# Schematic.net
KiCad netlist of a schematic drawn in Altium Designer
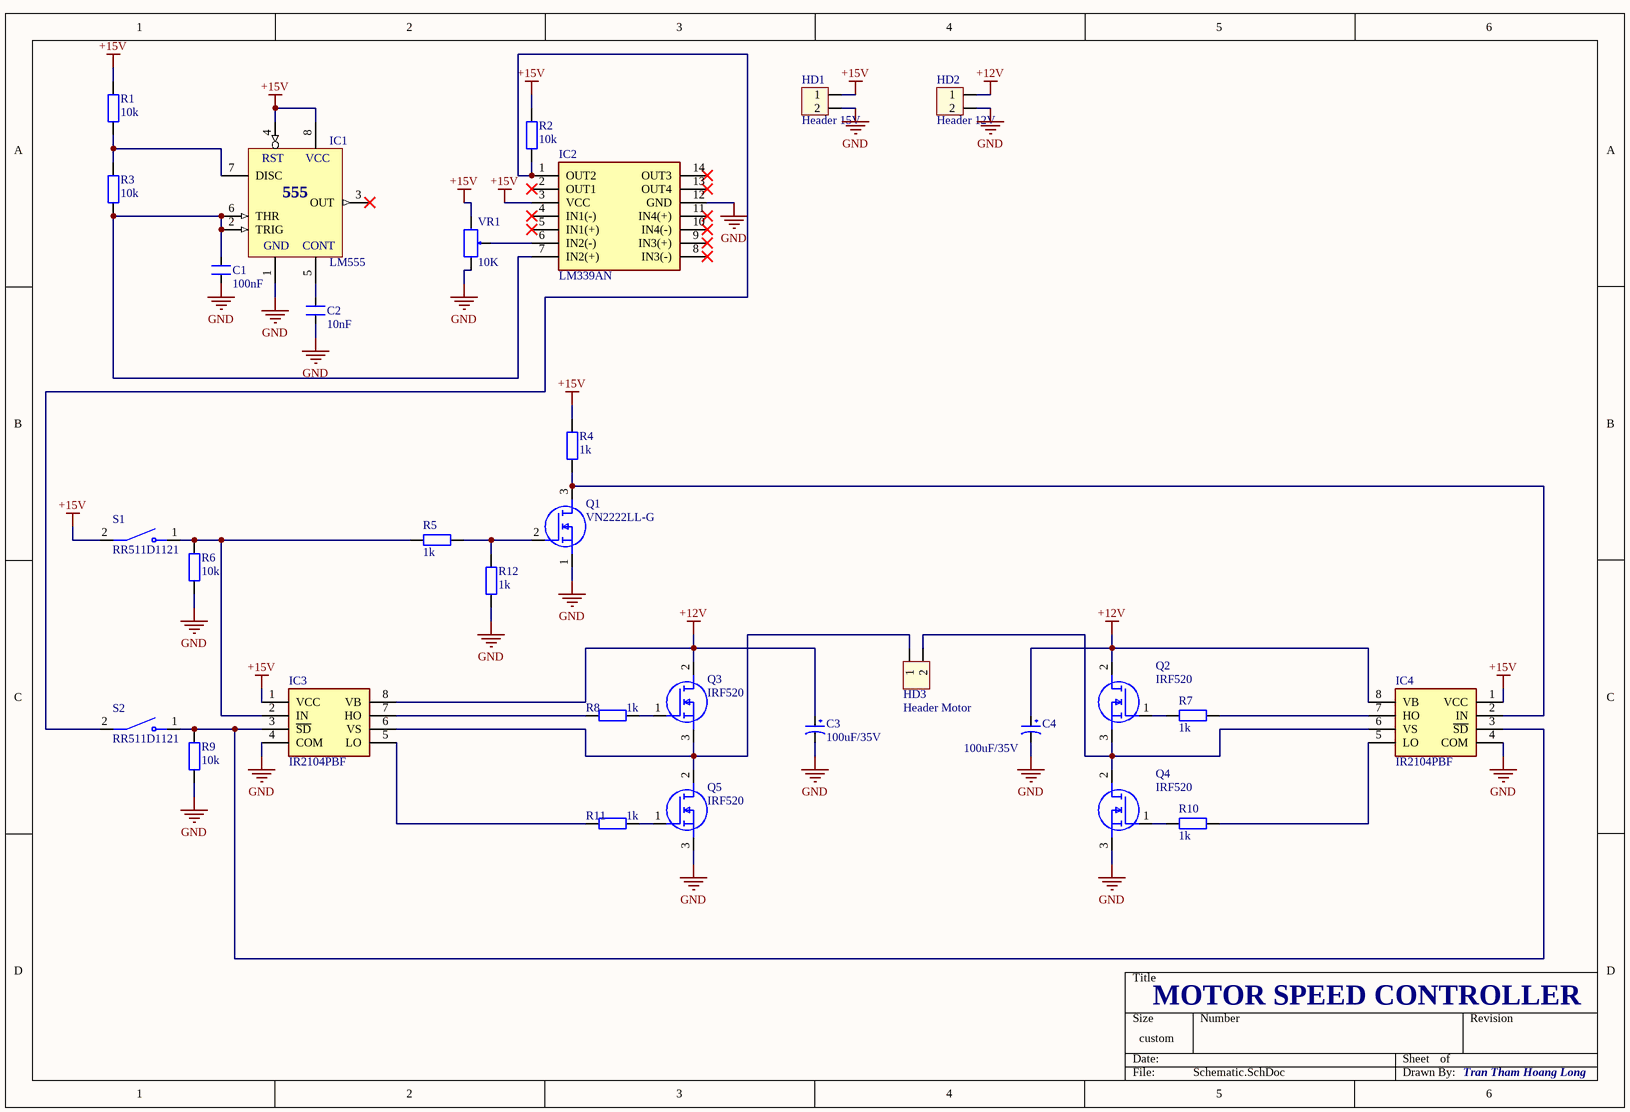
[diagram p0: Schematic.SchDoc]

(export (version "E")
  (design (tool "Eeschema 10.0.6"))
  (components
    (comp (ref "C1")
      (value "100nF")
      (footprint "CN1")
      (description "Cap np  1pF - 472pF")
      (libsource (lib "syhaunguyen") (part "CN1"))
    )
    (comp (ref "C2")
      (value "10nF")
      (footprint "CN1")
      (description "Cap np  1pF - 472pF")
      (libsource (lib "syhaunguyen") (part "CN1"))
    )
    (comp (ref "C3")
      (value "100uF/35V")
      (footprint "CP1.5/3.4")
      (description "Cap 100uF/35V - 470uF/16V")
      (libsource (lib "syhaunguyen") (part "CP3"))
    )
    (comp (ref "C4")
      (value "100uF/35V")
      (footprint "CP1.5/3.4")
      (description "Cap 100uF/35V - 470uF/16V")
      (libsource (lib "syhaunguyen") (part "CP3"))
    )
    (comp (ref "HD1")
      (value "Header 15V")
      (footprint "HED2")
      (description "Header 2 (Green)")
      (libsource (lib "syhaunguyen") (part "Hed2"))
    )
    (comp (ref "HD2")
      (value "Header 12V")
      (footprint "HED2")
      (description "Header 2 (Green)")
      (libsource (lib "syhaunguyen") (part "Hed2"))
    )
    (comp (ref "HD3")
      (value "Header Motor")
      (footprint "HED2")
      (description "Header 2 (Green)")
      (libsource (lib "") (part "Hed2_1"))
    )
    (comp (ref "IC1")
      (value "LM555")
      (footprint "DIP8/W0.3")
      (description "Timer")
      (libsource (lib "syhaunguyen") (part "LM555"))
    )
    (comp (ref "IC2")
      (value "LM339AN")
      (footprint "SamacSys:DIP794W56P254L1918H533Q14N")
      (description "Integrated Circuit")
      (fields (field (name "MOUSER PART NUMBER") "512-LM339AN"))
      (libsource (lib "*") (part "LM339AN"))
    )
    (comp (ref "IC3")
      (value "IR2104PBF")
      (footprint "SamacSys:DIP762W56P254L988H533Q8N")
      (description "Integrated Circuit")
      (fields (field (name "MOUSER PART NUMBER") "942-IR2104PBF"))
      (libsource (lib "") (part "IR2104PBF_1"))
    )
    (comp (ref "IC4")
      (value "IR2104PBF")
      (footprint "SamacSys:DIP762W56P254L988H533Q8N")
      (description "Integrated Circuit")
      (fields (field (name "MOUSER PART NUMBER") "942-IR2104PBF"))
      (libsource (lib "*") (part "IR2104PBF"))
    )
    (comp (ref "Q1")
      (value "VN2222LL-G")
      (footprint "QTO-92A")
      (description "MOSFET (N-Channel)")
      (fields (field (name "MOUSER PART NUMBER") "689-VN2222LL-G"))
      (libsource (lib "*") (part "VN2222LL-G"))
    )
    (comp (ref "Q2")
      (value "IRF520")
      (footprint "QTO-220H3")
      (description "MOSFET (N-Channel)")
      (fields (field (name "MOUSER PART NUMBER") "511-IRF520"))
      (libsource (lib "SamacSys") (part "IRF520"))
    )
    (comp (ref "Q3")
      (value "IRF520")
      (footprint "QTO-220H3")
      (description "MOSFET (N-Channel)")
      (fields (field (name "MOUSER PART NUMBER") "511-IRF520"))
      (libsource (lib "SamacSys") (part "IRF520"))
    )
    (comp (ref "Q4")
      (value "IRF520")
      (footprint "QTO-220H3")
      (description "MOSFET (N-Channel)")
      (fields (field (name "MOUSER PART NUMBER") "511-IRF520"))
      (libsource (lib "SamacSys") (part "IRF520"))
    )
    (comp (ref "Q5")
      (value "IRF520")
      (footprint "QTO-220H3")
      (description "MOSFET (N-Channel)")
      (fields (field (name "MOUSER PART NUMBER") "511-IRF520"))
      (libsource (lib "SamacSys") (part "IRF520"))
    )
    (comp (ref "R1")
      (value "10k")
      (footprint "R1/4W")
      (description "Resistor 1/4W")
      (libsource (lib "syhaunguyen") (part "R1/4W"))
    )
    (comp (ref "R2")
      (value "10k")
      (footprint "R1/4W")
      (description "Resistor 1/4W")
      (libsource (lib "syhaunguyen") (part "R1/4W"))
    )
    (comp (ref "R3")
      (value "10k")
      (footprint "R1/4W")
      (description "Resistor 1/4W")
      (libsource (lib "syhaunguyen") (part "R1/4W"))
    )
    (comp (ref "R4")
      (value "1k")
      (footprint "R1/4W")
      (description "Resistor 1/4W")
      (libsource (lib "syhaunguyen") (part "R1/4W"))
    )
    (comp (ref "R5")
      (value "1k")
      (footprint "R1/4W")
      (description "Resistor 1/4W")
      (libsource (lib "syhaunguyen") (part "R1/4W"))
    )
    (comp (ref "R6")
      (value "10k")
      (footprint "R1/4W")
      (description "Resistor 1/4W")
      (libsource (lib "syhaunguyen") (part "R1/4W"))
    )
    (comp (ref "R7")
      (value "1k")
      (footprint "R1/4W")
      (description "Resistor 1/4W")
      (libsource (lib "syhaunguyen") (part "R1/4W"))
    )
    (comp (ref "R8")
      (value "1k")
      (footprint "R1/4W")
      (description "Resistor 1/4W")
      (libsource (lib "syhaunguyen") (part "R1/4W"))
    )
    (comp (ref "R9")
      (value "10k")
      (footprint "R1/4W")
      (description "Resistor 1/4W")
      (libsource (lib "syhaunguyen") (part "R1/4W"))
    )
    (comp (ref "R10")
      (value "1k")
      (footprint "R1/4W")
      (description "Resistor 1/4W")
      (libsource (lib "syhaunguyen") (part "R1/4W"))
    )
    (comp (ref "R11")
      (value "1k")
      (footprint "R1/4W")
      (description "Resistor 1/4W")
      (libsource (lib "syhaunguyen") (part "R1/4W"))
    )
    (comp (ref "R12")
      (value "1k")
      (footprint "R1/4W")
      (description "Resistor 1/4W")
      (libsource (lib "syhaunguyen") (part "R1/4W"))
    )
    (comp (ref "S1")
      (value "RR511D1121")
      (footprint "E-SWITCH_RR511D1121")
      (description "Rocker Switch, RR5 Series, SPST,OFF-ON,Blk Rocker,I/O Legend, 20A, 125VAC, QC")
      (fields (field (name "MF") "E-Switch"))
      (libsource (lib "RR511D1121") (part "RR511D1121"))
    )
    (comp (ref "S2")
      (value "RR511D1121")
      (footprint "E-SWITCH_RR511D1121")
      (description "Rocker Switch, RR5 Series, SPST,OFF-ON,Blk Rocker,I/O Legend, 20A, 125VAC, QC")
      (fields (field (name "MF") "E-Switch"))
      (libsource (lib "RR511D1121") (part "RR511D1121"))
    )
    (comp (ref "VR1")
      (value "10K")
      (footprint "VOL_1")
      (description "Var Resistor")
      (libsource (lib "Cty1") (part "Var Resitor"))
    )
  )
  (nets
    (net (code "1") (name "+12V") (class "Default")
      (node (ref "C3") (pin "1") (pinfunction "1_1") (pintype "passive"))
      (node (ref "C4") (pin "1") (pinfunction "1_1") (pintype "passive"))
      (node (ref "HD2") (pin "1") (pinfunction "1_1") (pintype "passive"))
      (node (ref "IC3") (pin "8") (pinfunction "VB_8") (pintype "passive"))
      (node (ref "IC4") (pin "8") (pinfunction "VB_8") (pintype "passive"))
      (node (ref "Q2") (pin "2") (pinfunction "D_2") (pintype "passive"))
      (node (ref "Q3") (pin "2") (pinfunction "D_2") (pintype "passive"))
    )
    (net (code "2") (name "+15V") (class "Default")
      (node (ref "HD1") (pin "1") (pinfunction "1_1") (pintype "passive"))
      (node (ref "IC1") (pin "4") (pinfunction "RST_4") (pintype "input"))
      (node (ref "IC1") (pin "8") (pinfunction "VCC_8") (pintype "power_in"))
      (node (ref "IC2") (pin "3") (pinfunction "VCC_3") (pintype "passive"))
      (node (ref "IC3") (pin "1") (pinfunction "VCC_1") (pintype "passive"))
      (node (ref "IC4") (pin "1") (pinfunction "VCC_1") (pintype "passive"))
      (node (ref "R1") (pin "2") (pinfunction "2_2") (pintype "passive"))
      (node (ref "R2") (pin "2") (pinfunction "2_2") (pintype "passive"))
      (node (ref "R4") (pin "1") (pinfunction "1_1") (pintype "passive"))
      (node (ref "S1") (pin "2") (pinfunction "COM_2") (pintype "passive"))
      (node (ref "VR1") (pin "1") (pinfunction "1_1") (pintype "passive"))
    )
    (net (code "3") (name "GND") (class "Default")
      (node (ref "C1") (pin "1") (pinfunction "1_1") (pintype "passive"))
      (node (ref "C2") (pin "1") (pinfunction "1_1") (pintype "passive"))
      (node (ref "C3") (pin "2") (pinfunction "2_2") (pintype "passive"))
      (node (ref "C4") (pin "2") (pinfunction "2_2") (pintype "passive"))
      (node (ref "HD1") (pin "2") (pinfunction "2_2") (pintype "passive"))
      (node (ref "HD2") (pin "2") (pinfunction "2_2") (pintype "passive"))
      (node (ref "IC1") (pin "1") (pinfunction "GND_1") (pintype "power_in"))
      (node (ref "IC2") (pin "12") (pinfunction "GND_12") (pintype "passive"))
      (node (ref "IC3") (pin "4") (pinfunction "COM_4") (pintype "passive"))
      (node (ref "IC4") (pin "4") (pinfunction "COM_4") (pintype "passive"))
      (node (ref "Q1") (pin "1") (pinfunction "S_1") (pintype "passive"))
      (node (ref "Q4") (pin "3") (pinfunction "S_3") (pintype "passive"))
      (node (ref "Q5") (pin "3") (pinfunction "S_3") (pintype "passive"))
      (node (ref "R12") (pin "2") (pinfunction "2_2") (pintype "passive"))
      (node (ref "R6") (pin "1") (pinfunction "1_1") (pintype "passive"))
      (node (ref "R9") (pin "1") (pinfunction "1_1") (pintype "passive"))
      (node (ref "VR1") (pin "3") (pinfunction "3_3") (pintype "passive"))
    )
    (net (code "4") (name "Net-(IC1-CONT)") (class "Default")
      (node (ref "C2") (pin "2") (pinfunction "2_2") (pintype "passive"))
      (node (ref "IC1") (pin "5") (pinfunction "CONT_5") (pintype "passive"))
    )
    (net (code "5") (name "Net-(IC1-DISC)") (class "Default")
      (node (ref "IC1") (pin "7") (pinfunction "DISC_7") (pintype "open_collector"))
      (node (ref "R1") (pin "1") (pinfunction "1_1") (pintype "passive"))
      (node (ref "R3") (pin "2") (pinfunction "2_2") (pintype "passive"))
    )
    (net (code "6") (name "Net-(IC1-THR)") (class "Default")
      (node (ref "C1") (pin "2") (pinfunction "2_2") (pintype "passive"))
      (node (ref "IC1") (pin "2") (pinfunction "TRIG_2") (pintype "input"))
      (node (ref "IC1") (pin "6") (pinfunction "THR_6") (pintype "input"))
      (node (ref "IC2") (pin "7") (pinfunction "IN2(+)_7") (pintype "passive"))
      (node (ref "R3") (pin "1") (pinfunction "1_1") (pintype "passive"))
    )
    (net (code "7") (name "Net-(IC2-IN2(-))") (class "Default")
      (node (ref "IC2") (pin "6") (pinfunction "IN2(-)_6") (pintype "passive"))
      (node (ref "VR1") (pin "2") (pinfunction "2_2") (pintype "passive"))
    )
    (net (code "8") (name "Net-(IC2-OUT2)") (class "Default")
      (node (ref "IC2") (pin "1") (pinfunction "OUT2_1") (pintype "passive"))
      (node (ref "R2") (pin "1") (pinfunction "1_1") (pintype "passive"))
      (node (ref "S2") (pin "2") (pinfunction "COM_2") (pintype "passive"))
    )
    (net (code "9") (name "Net-(IC3-HO)") (class "Default")
      (node (ref "IC3") (pin "7") (pinfunction "HO_7") (pintype "passive"))
      (node (ref "R8") (pin "2") (pinfunction "2_2") (pintype "passive"))
    )
    (net (code "10") (name "Net-(IC3-IN)") (class "Default")
      (node (ref "IC3") (pin "2") (pinfunction "IN_2") (pintype "passive"))
      (node (ref "R5") (pin "2") (pinfunction "2_2") (pintype "passive"))
      (node (ref "R6") (pin "2") (pinfunction "2_2") (pintype "passive"))
      (node (ref "S1") (pin "1") (pinfunction "NO_1") (pintype "passive"))
    )
    (net (code "11") (name "Net-(IC3-LO)") (class "Default")
      (node (ref "IC3") (pin "5") (pinfunction "LO_5") (pintype "passive"))
      (node (ref "R11") (pin "2") (pinfunction "2_2") (pintype "passive"))
    )
    (net (code "12") (name "Net-(IC3-VS)") (class "Default")
      (node (ref "HD3") (pin "1") (pinfunction "1_1") (pintype "passive"))
      (node (ref "IC3") (pin "6") (pinfunction "VS_6") (pintype "passive"))
      (node (ref "Q3") (pin "3") (pinfunction "S_3") (pintype "passive"))
      (node (ref "Q5") (pin "2") (pinfunction "D_2") (pintype "passive"))
    )
    (net (code "13") (name "Net-(IC3-~{SD})") (class "Default")
      (node (ref "IC3") (pin "3") (pinfunction "~{SD}_3") (pintype "passive"))
      (node (ref "IC4") (pin "3") (pinfunction "~{SD}_3") (pintype "passive"))
      (node (ref "R9") (pin "2") (pinfunction "2_2") (pintype "passive"))
      (node (ref "S2") (pin "1") (pinfunction "NO_1") (pintype "passive"))
    )
    (net (code "14") (name "Net-(IC4-HO)") (class "Default")
      (node (ref "IC4") (pin "7") (pinfunction "HO_7") (pintype "passive"))
      (node (ref "R7") (pin "2") (pinfunction "2_2") (pintype "passive"))
    )
    (net (code "15") (name "Net-(IC4-IN)") (class "Default")
      (node (ref "IC4") (pin "2") (pinfunction "IN_2") (pintype "passive"))
      (node (ref "Q1") (pin "3") (pinfunction "D_3") (pintype "passive"))
      (node (ref "R4") (pin "2") (pinfunction "2_2") (pintype "passive"))
    )
    (net (code "16") (name "Net-(IC4-LO)") (class "Default")
      (node (ref "IC4") (pin "5") (pinfunction "LO_5") (pintype "passive"))
      (node (ref "R10") (pin "2") (pinfunction "2_2") (pintype "passive"))
    )
    (net (code "17") (name "Net-(IC4-VS)") (class "Default")
      (node (ref "HD3") (pin "2") (pinfunction "2_2") (pintype "passive"))
      (node (ref "IC4") (pin "6") (pinfunction "VS_6") (pintype "passive"))
      (node (ref "Q2") (pin "3") (pinfunction "S_3") (pintype "passive"))
      (node (ref "Q4") (pin "2") (pinfunction "D_2") (pintype "passive"))
    )
    (net (code "18") (name "Net-(Q1-G)") (class "Default")
      (node (ref "Q1") (pin "2") (pinfunction "G_2") (pintype "passive"))
      (node (ref "R12") (pin "1") (pinfunction "1_1") (pintype "passive"))
      (node (ref "R5") (pin "1") (pinfunction "1_1") (pintype "passive"))
    )
    (net (code "19") (name "Net-(Q2-G)") (class "Default")
      (node (ref "Q2") (pin "1") (pinfunction "G_1") (pintype "passive"))
      (node (ref "R7") (pin "1") (pinfunction "1_1") (pintype "passive"))
    )
    (net (code "20") (name "Net-(Q3-G)") (class "Default")
      (node (ref "Q3") (pin "1") (pinfunction "G_1") (pintype "passive"))
      (node (ref "R8") (pin "1") (pinfunction "1_1") (pintype "passive"))
    )
    (net (code "21") (name "Net-(Q4-G)") (class "Default")
      (node (ref "Q4") (pin "1") (pinfunction "G_1") (pintype "passive"))
      (node (ref "R10") (pin "1") (pinfunction "1_1") (pintype "passive"))
    )
    (net (code "22") (name "Net-(Q5-G)") (class "Default")
      (node (ref "Q5") (pin "1") (pinfunction "G_1") (pintype "passive"))
      (node (ref "R11") (pin "1") (pinfunction "1_1") (pintype "passive"))
    )
    (net (code "23") (name "unconnected-(IC1-OUT-Pad3)") (class "Default")
      (node (ref "IC1") (pin "3") (pinfunction "OUT_3") (pintype "output+no_connect"))
    )
    (net (code "24") (name "unconnected-(IC2-IN1(+)-Pad5)") (class "Default")
      (node (ref "IC2") (pin "5") (pinfunction "IN1(+)_5") (pintype "passive+no_connect"))
    )
    (net (code "25") (name "unconnected-(IC2-IN1(-)-Pad4)") (class "Default")
      (node (ref "IC2") (pin "4") (pinfunction "IN1(-)_4") (pintype "passive+no_connect"))
    )
    (net (code "26") (name "unconnected-(IC2-IN3(+)-Pad9)") (class "Default")
      (node (ref "IC2") (pin "9") (pinfunction "IN3(+)_9") (pintype "passive+no_connect"))
    )
    (net (code "27") (name "unconnected-(IC2-IN3(-)-Pad8)") (class "Default")
      (node (ref "IC2") (pin "8") (pinfunction "IN3(-)_8") (pintype "passive+no_connect"))
    )
    (net (code "28") (name "unconnected-(IC2-IN4(+)-Pad11)") (class "Default")
      (node (ref "IC2") (pin "11") (pinfunction "IN4(+)_11") (pintype "passive+no_connect"))
    )
    (net (code "29") (name "unconnected-(IC2-IN4(-)-Pad10)") (class "Default")
      (node (ref "IC2") (pin "10") (pinfunction "IN4(-)_10") (pintype "passive+no_connect"))
    )
    (net (code "30") (name "unconnected-(IC2-OUT1-Pad2)") (class "Default")
      (node (ref "IC2") (pin "2") (pinfunction "OUT1_2") (pintype "passive+no_connect"))
    )
    (net (code "31") (name "unconnected-(IC2-OUT3-Pad14)") (class "Default")
      (node (ref "IC2") (pin "14") (pinfunction "OUT3_14") (pintype "passive+no_connect"))
    )
    (net (code "32") (name "unconnected-(IC2-OUT4-Pad13)") (class "Default")
      (node (ref "IC2") (pin "13") (pinfunction "OUT4_13") (pintype "passive+no_connect"))
    )
  )
)
